# Py_car_2021-02-27.net
KiCad netlist of a schematic drawn in EasyEDA
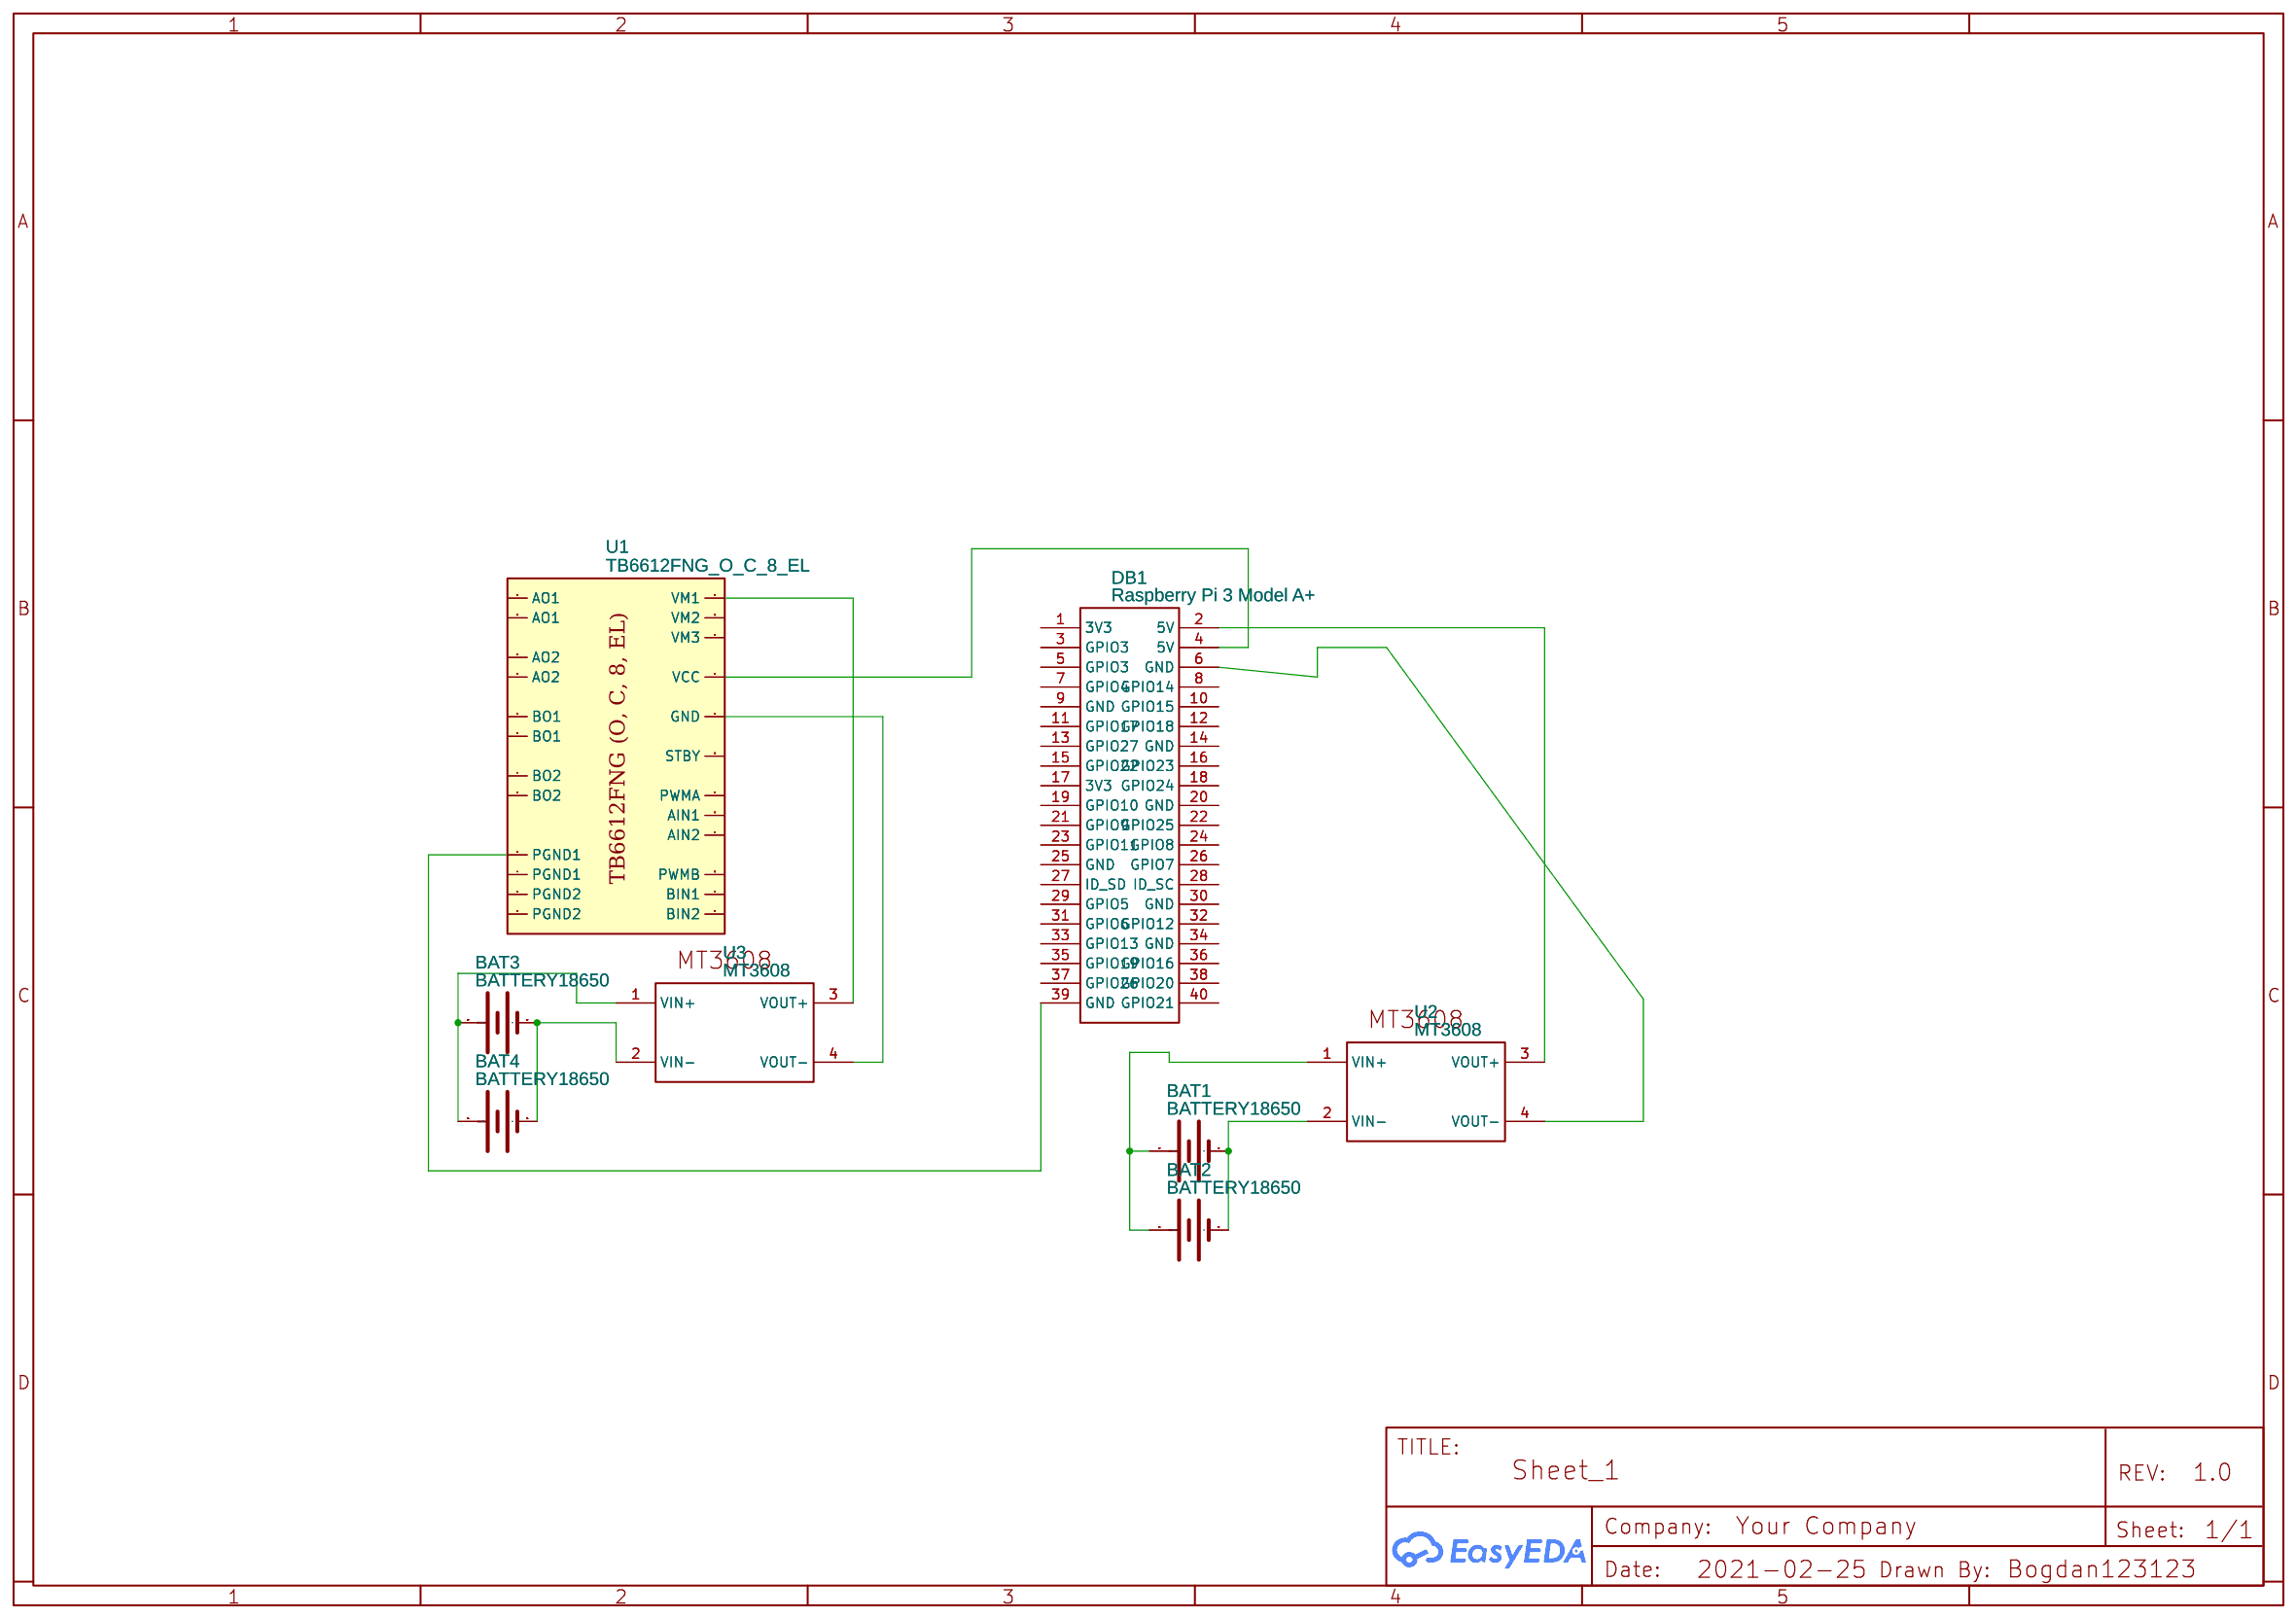
[diagram p0: schematic sheet]

(export (version "E")
  (design (tool "Eeschema 10.0.6"))
  (components
    (comp (ref "BAT1") (value "BATTERY18650") (libsource (lib "") (part "BATTERY18650")))
    (comp (ref "BAT2") (value "BATTERY18650") (libsource (lib "") (part "BATTERY18650")))
    (comp (ref "BAT3") (value "BATTERY18650") (libsource (lib "") (part "BATTERY18650")))
    (comp (ref "BAT4") (value "BATTERY18650") (libsource (lib "") (part "BATTERY18650")))
    (comp (ref "DB1")
      (value "Raspberry Pi 3 Model A+")
      (fields
        (field (name "BOM_Manufacturer Part") "RPI3-MODAP")
        (field (name "BOM_Supplier Part") "2946269")
      )
      (libsource (lib "") (part "Raspberry Pi 3 Model A+"))
    )
    (comp (ref "U1") (value "TB6612FNG_O_C_8_EL") (libsource (lib "") (part "TB6612FNG_O_C_8_EL")))
    (comp (ref "U2") (value "MT3608") (libsource (lib "") (part "MT3608")))
    (comp (ref "U3") (value "MT3608") (libsource (lib "") (part "MT3608")))
  )
  (nets
    (net (code "1") (name "Net-(BAT1-+)") (class "Default")
      (node (ref "BAT1") (pin "PWR@1") (pinfunction "+_PWR@1") (pintype "passive"))
      (node (ref "BAT2") (pin "PWR@1") (pinfunction "+_PWR@1") (pintype "passive"))
      (node (ref "U2") (pin "1") (pinfunction "VIN+_1") (pintype "unspecified"))
    )
    (net (code "2") (name "Net-(BAT1--)") (class "Default")
      (node (ref "BAT1") (pin "GND@1") (pinfunction "-_GND@1") (pintype "passive"))
      (node (ref "BAT2") (pin "GND@1") (pinfunction "-_GND@1") (pintype "passive"))
      (node (ref "U2") (pin "2") (pinfunction "VIN-_2") (pintype "unspecified"))
    )
    (net (code "3") (name "Net-(BAT3-+)") (class "Default")
      (node (ref "BAT3") (pin "PWR@1") (pinfunction "+_PWR@1") (pintype "passive"))
      (node (ref "BAT4") (pin "PWR@1") (pinfunction "+_PWR@1") (pintype "passive"))
      (node (ref "U3") (pin "1") (pinfunction "VIN+_1") (pintype "unspecified"))
    )
    (net (code "4") (name "Net-(BAT3--)") (class "Default")
      (node (ref "BAT3") (pin "GND@1") (pinfunction "-_GND@1") (pintype "passive"))
      (node (ref "BAT4") (pin "GND@1") (pinfunction "-_GND@1") (pintype "passive"))
      (node (ref "U3") (pin "2") (pinfunction "VIN-_2") (pintype "unspecified"))
    )
    (net (code "5") (name "Net-(DB1-GND-Pad39)") (class "Default")
      (node (ref "DB1") (pin "39") (pinfunction "GND_39") (pintype "unspecified"))
      (node (ref "U1") (pin "3") (pinfunction "PGND1_3") (pintype "unspecified"))
    )
    (net (code "6") (name "Net-(U1-GND)") (class "Default")
      (node (ref "U1") (pin "18") (pinfunction "GND_18") (pintype "unspecified"))
      (node (ref "U3") (pin "4") (pinfunction "VOUT-_4") (pintype "unspecified"))
    )
    (net (code "7") (name "Net-(U1-VCC)") (class "Default")
      (node (ref "DB1") (pin "4") (pinfunction "5V_4") (pintype "unspecified"))
      (node (ref "U1") (pin "20") (pinfunction "VCC_20") (pintype "unspecified"))
    )
    (net (code "8") (name "Net-(U1-VM1)") (class "Default")
      (node (ref "U1") (pin "24") (pinfunction "VM1_24") (pintype "unspecified"))
      (node (ref "U3") (pin "3") (pinfunction "VOUT+_3") (pintype "unspecified"))
    )
    (net (code "9") (name "Net-(U2-VOUT+)") (class "Default")
      (node (ref "DB1") (pin "2") (pinfunction "5V_2") (pintype "unspecified"))
      (node (ref "U2") (pin "3") (pinfunction "VOUT+_3") (pintype "unspecified"))
    )
    (net (code "10") (name "Net-(U2-VOUT-)") (class "Default")
      (node (ref "DB1") (pin "6") (pinfunction "GND_6") (pintype "unspecified"))
      (node (ref "U2") (pin "4") (pinfunction "VOUT-_4") (pintype "unspecified"))
    )
    (net (code "11") (name "unconnected-(DB1-3V3-Pad1)") (class "Default")
      (node (ref "DB1") (pin "1") (pinfunction "3V3_1") (pintype "unspecified"))
    )
    (net (code "12") (name "unconnected-(DB1-3V3-Pad17)") (class "Default")
      (node (ref "DB1") (pin "17") (pinfunction "3V3_17") (pintype "unspecified"))
    )
    (net (code "13") (name "unconnected-(DB1-GND-Pad9)") (class "Default")
      (node (ref "DB1") (pin "9") (pinfunction "GND_9") (pintype "unspecified"))
    )
    (net (code "14") (name "unconnected-(DB1-GND-Pad14)") (class "Default")
      (node (ref "DB1") (pin "14") (pinfunction "GND_14") (pintype "unspecified"))
    )
    (net (code "15") (name "unconnected-(DB1-GND-Pad20)") (class "Default")
      (node (ref "DB1") (pin "20") (pinfunction "GND_20") (pintype "unspecified"))
    )
    (net (code "16") (name "unconnected-(DB1-GND-Pad25)") (class "Default")
      (node (ref "DB1") (pin "25") (pinfunction "GND_25") (pintype "unspecified"))
    )
    (net (code "17") (name "unconnected-(DB1-GND-Pad30)") (class "Default")
      (node (ref "DB1") (pin "30") (pinfunction "GND_30") (pintype "unspecified"))
    )
    (net (code "18") (name "unconnected-(DB1-GND-Pad34)") (class "Default")
      (node (ref "DB1") (pin "34") (pinfunction "GND_34") (pintype "unspecified"))
    )
    (net (code "19") (name "unconnected-(DB1-GPIO3-Pad3)") (class "Default")
      (node (ref "DB1") (pin "3") (pinfunction "GPIO3_3") (pintype "bidirectional"))
    )
    (net (code "20") (name "unconnected-(DB1-GPIO3-Pad5)") (class "Default")
      (node (ref "DB1") (pin "5") (pinfunction "GPIO3_5") (pintype "bidirectional"))
    )
    (net (code "21") (name "unconnected-(DB1-GPIO4-Pad7)") (class "Default")
      (node (ref "DB1") (pin "7") (pinfunction "GPIO4_7") (pintype "bidirectional"))
    )
    (net (code "22") (name "unconnected-(DB1-GPIO5-Pad29)") (class "Default")
      (node (ref "DB1") (pin "29") (pinfunction "GPIO5_29") (pintype "bidirectional"))
    )
    (net (code "23") (name "unconnected-(DB1-GPIO6-Pad31)") (class "Default")
      (node (ref "DB1") (pin "31") (pinfunction "GPIO6_31") (pintype "bidirectional"))
    )
    (net (code "24") (name "unconnected-(DB1-GPIO7-Pad26)") (class "Default")
      (node (ref "DB1") (pin "26") (pinfunction "GPIO7_26") (pintype "bidirectional"))
    )
    (net (code "25") (name "unconnected-(DB1-GPIO8-Pad24)") (class "Default")
      (node (ref "DB1") (pin "24") (pinfunction "GPIO8_24") (pintype "bidirectional"))
    )
    (net (code "26") (name "unconnected-(DB1-GPIO9-Pad21)") (class "Default")
      (node (ref "DB1") (pin "21") (pinfunction "GPIO9_21") (pintype "bidirectional"))
    )
    (net (code "27") (name "unconnected-(DB1-GPIO10-Pad19)") (class "Default")
      (node (ref "DB1") (pin "19") (pinfunction "GPIO10_19") (pintype "bidirectional"))
    )
    (net (code "28") (name "unconnected-(DB1-GPIO11-Pad23)") (class "Default")
      (node (ref "DB1") (pin "23") (pinfunction "GPIO11_23") (pintype "bidirectional"))
    )
    (net (code "29") (name "unconnected-(DB1-GPIO12-Pad32)") (class "Default")
      (node (ref "DB1") (pin "32") (pinfunction "GPIO12_32") (pintype "bidirectional"))
    )
    (net (code "30") (name "unconnected-(DB1-GPIO13-Pad33)") (class "Default")
      (node (ref "DB1") (pin "33") (pinfunction "GPIO13_33") (pintype "bidirectional"))
    )
    (net (code "31") (name "unconnected-(DB1-GPIO14-Pad8)") (class "Default")
      (node (ref "DB1") (pin "8") (pinfunction "GPIO14_8") (pintype "bidirectional"))
    )
    (net (code "32") (name "unconnected-(DB1-GPIO15-Pad10)") (class "Default")
      (node (ref "DB1") (pin "10") (pinfunction "GPIO15_10") (pintype "bidirectional"))
    )
    (net (code "33") (name "unconnected-(DB1-GPIO16-Pad36)") (class "Default")
      (node (ref "DB1") (pin "36") (pinfunction "GPIO16_36") (pintype "bidirectional"))
    )
    (net (code "34") (name "unconnected-(DB1-GPIO17-Pad11)") (class "Default")
      (node (ref "DB1") (pin "11") (pinfunction "GPIO17_11") (pintype "bidirectional"))
    )
    (net (code "35") (name "unconnected-(DB1-GPIO18-Pad12)") (class "Default")
      (node (ref "DB1") (pin "12") (pinfunction "GPIO18_12") (pintype "bidirectional"))
    )
    (net (code "36") (name "unconnected-(DB1-GPIO19-Pad35)") (class "Default")
      (node (ref "DB1") (pin "35") (pinfunction "GPIO19_35") (pintype "bidirectional"))
    )
    (net (code "37") (name "unconnected-(DB1-GPIO20-Pad38)") (class "Default")
      (node (ref "DB1") (pin "38") (pinfunction "GPIO20_38") (pintype "bidirectional"))
    )
    (net (code "38") (name "unconnected-(DB1-GPIO21-Pad40)") (class "Default")
      (node (ref "DB1") (pin "40") (pinfunction "GPIO21_40") (pintype "bidirectional"))
    )
    (net (code "39") (name "unconnected-(DB1-GPIO22-Pad15)") (class "Default")
      (node (ref "DB1") (pin "15") (pinfunction "GPIO22_15") (pintype "bidirectional"))
    )
    (net (code "40") (name "unconnected-(DB1-GPIO23-Pad16)") (class "Default")
      (node (ref "DB1") (pin "16") (pinfunction "GPIO23_16") (pintype "bidirectional"))
    )
    (net (code "41") (name "unconnected-(DB1-GPIO24-Pad18)") (class "Default")
      (node (ref "DB1") (pin "18") (pinfunction "GPIO24_18") (pintype "bidirectional"))
    )
    (net (code "42") (name "unconnected-(DB1-GPIO25-Pad22)") (class "Default")
      (node (ref "DB1") (pin "22") (pinfunction "GPIO25_22") (pintype "bidirectional"))
    )
    (net (code "43") (name "unconnected-(DB1-GPIO26-Pad37)") (class "Default")
      (node (ref "DB1") (pin "37") (pinfunction "GPIO26_37") (pintype "bidirectional"))
    )
    (net (code "44") (name "unconnected-(DB1-GPIO27-Pad13)") (class "Default")
      (node (ref "DB1") (pin "13") (pinfunction "GPIO27_13") (pintype "bidirectional"))
    )
    (net (code "45") (name "unconnected-(DB1-ID_SC-Pad28)") (class "Default")
      (node (ref "DB1") (pin "28") (pinfunction "ID_SC_28") (pintype "unspecified"))
    )
    (net (code "46") (name "unconnected-(DB1-ID_SD-Pad27)") (class "Default")
      (node (ref "DB1") (pin "27") (pinfunction "ID_SD_27") (pintype "unspecified"))
    )
    (net (code "47") (name "unconnected-(U1-AIN1-Pad21)") (class "Default")
      (node (ref "U1") (pin "21") (pinfunction "AIN1_21") (pintype "unspecified"))
    )
    (net (code "48") (name "unconnected-(U1-AIN2-Pad22)") (class "Default")
      (node (ref "U1") (pin "22") (pinfunction "AIN2_22") (pintype "unspecified"))
    )
    (net (code "49") (name "unconnected-(U1-AO1-Pad1)") (class "Default")
      (node (ref "U1") (pin "1") (pinfunction "AO1_1") (pintype "unspecified"))
    )
    (net (code "50") (name "unconnected-(U1-AO1-Pad2)") (class "Default")
      (node (ref "U1") (pin "2") (pinfunction "AO1_2") (pintype "unspecified"))
    )
    (net (code "51") (name "unconnected-(U1-AO2-Pad5)") (class "Default")
      (node (ref "U1") (pin "5") (pinfunction "AO2_5") (pintype "unspecified"))
    )
    (net (code "52") (name "unconnected-(U1-AO2-Pad6)") (class "Default")
      (node (ref "U1") (pin "6") (pinfunction "AO2_6") (pintype "unspecified"))
    )
    (net (code "53") (name "unconnected-(U1-BIN1-Pad17)") (class "Default")
      (node (ref "U1") (pin "17") (pinfunction "BIN1_17") (pintype "unspecified"))
    )
    (net (code "54") (name "unconnected-(U1-BIN2-Pad16)") (class "Default")
      (node (ref "U1") (pin "16") (pinfunction "BIN2_16") (pintype "unspecified"))
    )
    (net (code "55") (name "unconnected-(U1-BO1-Pad11)") (class "Default")
      (node (ref "U1") (pin "11") (pinfunction "BO1_11") (pintype "unspecified"))
    )
    (net (code "56") (name "unconnected-(U1-BO1-Pad12)") (class "Default")
      (node (ref "U1") (pin "12") (pinfunction "BO1_12") (pintype "unspecified"))
    )
    (net (code "57") (name "unconnected-(U1-BO2-Pad7)") (class "Default")
      (node (ref "U1") (pin "7") (pinfunction "BO2_7") (pintype "unspecified"))
    )
    (net (code "58") (name "unconnected-(U1-BO2-Pad8)") (class "Default")
      (node (ref "U1") (pin "8") (pinfunction "BO2_8") (pintype "unspecified"))
    )
    (net (code "59") (name "unconnected-(U1-PGND1-Pad4)") (class "Default")
      (node (ref "U1") (pin "4") (pinfunction "PGND1_4") (pintype "unspecified"))
    )
    (net (code "60") (name "unconnected-(U1-PGND2-Pad9)") (class "Default")
      (node (ref "U1") (pin "9") (pinfunction "PGND2_9") (pintype "unspecified"))
    )
    (net (code "61") (name "unconnected-(U1-PGND2-Pad10)") (class "Default")
      (node (ref "U1") (pin "10") (pinfunction "PGND2_10") (pintype "unspecified"))
    )
    (net (code "62") (name "unconnected-(U1-PWMA-Pad23)") (class "Default")
      (node (ref "U1") (pin "23") (pinfunction "PWMA_23") (pintype "unspecified"))
    )
    (net (code "63") (name "unconnected-(U1-PWMB-Pad15)") (class "Default")
      (node (ref "U1") (pin "15") (pinfunction "PWMB_15") (pintype "unspecified"))
    )
    (net (code "64") (name "unconnected-(U1-STBY-Pad19)") (class "Default")
      (node (ref "U1") (pin "19") (pinfunction "STBY_19") (pintype "unspecified"))
    )
    (net (code "65") (name "unconnected-(U1-VM2-Pad13)") (class "Default")
      (node (ref "U1") (pin "13") (pinfunction "VM2_13") (pintype "unspecified"))
    )
    (net (code "66") (name "unconnected-(U1-VM3-Pad14)") (class "Default")
      (node (ref "U1") (pin "14") (pinfunction "VM3_14") (pintype "unspecified"))
    )
  )
)
